# DSO_Front.net
KiCad netlist of a schematic drawn in Altium Designer
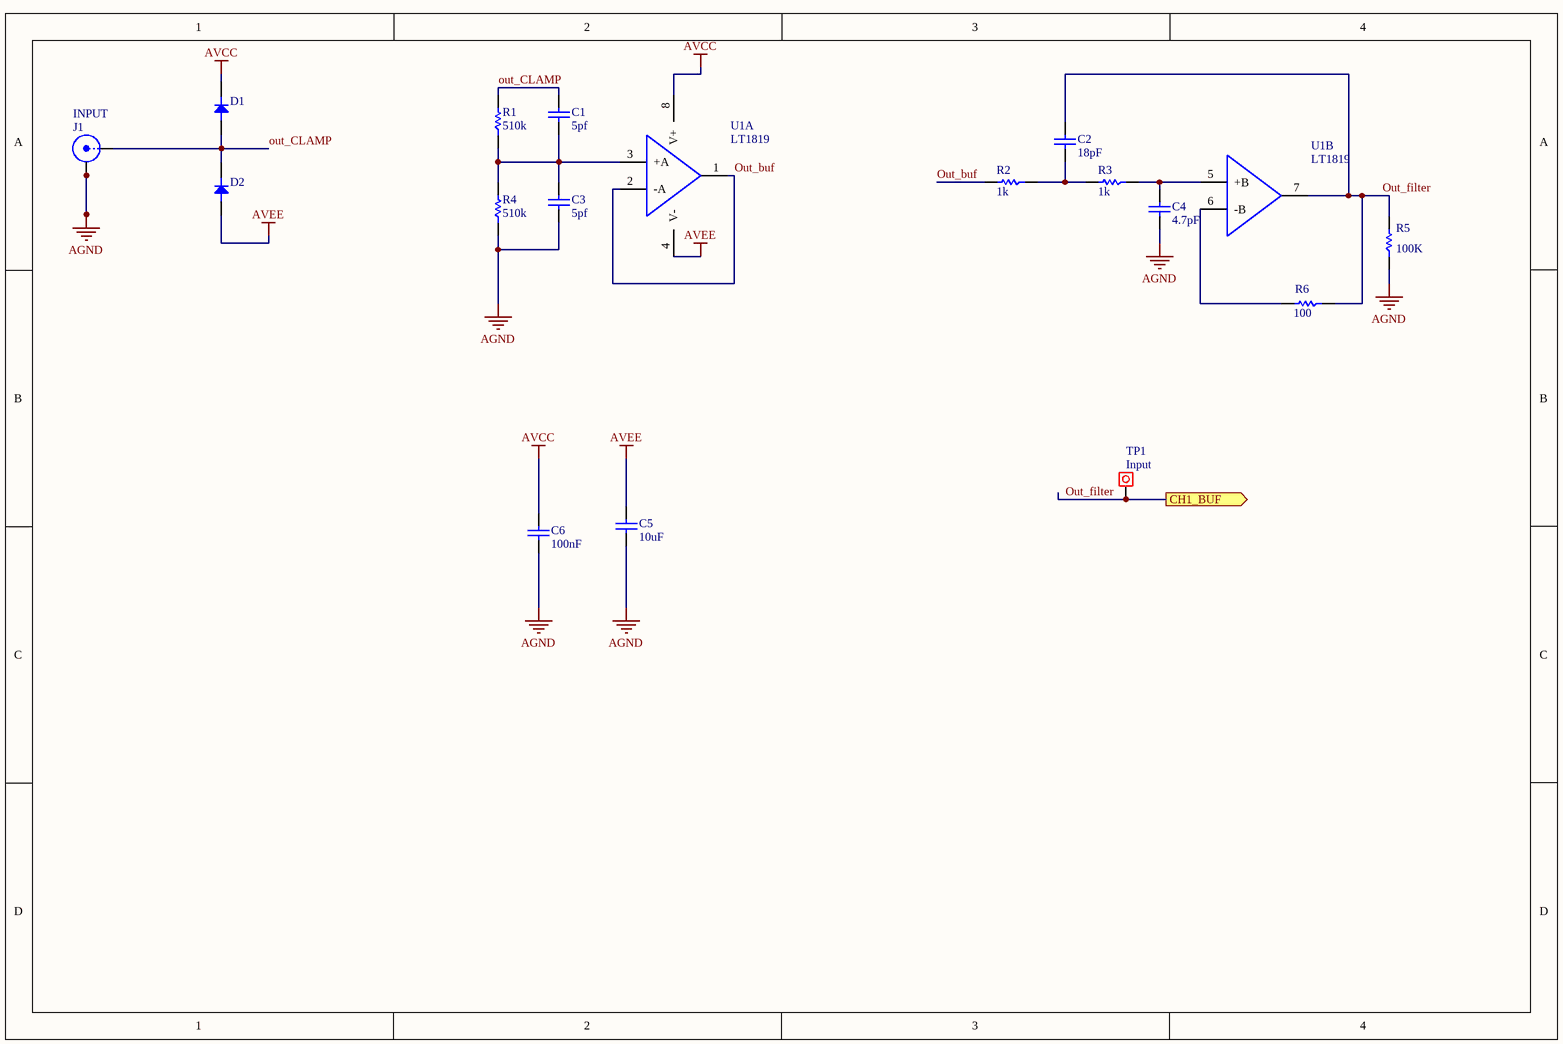
[diagram p0: DSO_Front.SchDoc]

(export (version "E")
  (design (tool "Eeschema 10.0.6"))
  (components
    (comp (ref "C1")
      (value "5pf")
      (footprint "0805C")
      (description "Capacitor")
      (fields (field (name "REVIEWED BY") "RM - 2018/08/05"))
      (libsource (lib "DSO") (part "C"))
    )
    (comp (ref "C2")
      (value "18pF")
      (footprint "0805C")
      (description "Capacitor")
      (fields (field (name "REVIEWED BY") "RM - 2018/08/05"))
      (libsource (lib "DSO") (part "C"))
    )
    (comp (ref "C3")
      (value "5pf")
      (footprint "0805C")
      (description "Capacitor")
      (fields (field (name "REVIEWED BY") "RM - 2018/08/05"))
      (libsource (lib "DSO") (part "C"))
    )
    (comp (ref "C4")
      (value "4.7pF")
      (footprint "0805C")
      (description "Capacitor")
      (fields (field (name "REVIEWED BY") "RM - 2018/08/05"))
      (libsource (lib "DSO") (part "C"))
    )
    (comp (ref "C5")
      (value "10uF")
      (footprint "0805C")
      (description "Capacitor")
      (fields (field (name "REVIEWED BY") "RM - 2018/08/05"))
      (libsource (lib "DSO") (part "C"))
    )
    (comp (ref "C6")
      (value "100nF")
      (footprint "0805C")
      (description "Capacitor")
      (fields (field (name "REVIEWED BY") "RM - 2018/08/05"))
      (libsource (lib "DSO") (part "C"))
    )
    (comp (ref "D1")
      (value "Diode")
      (footprint "SOD-123")
      (fields (field (name "REVIEWED BY") "RM - 2018/08/05"))
      (libsource (lib "DSO") (part "D"))
    )
    (comp (ref "D2")
      (value "Diode")
      (footprint "SOD-123")
      (fields (field (name "REVIEWED BY") "RM - 2018/08/05"))
      (libsource (lib "DSO") (part "D"))
    )
    (comp (ref "J1")
      (value "INPUT")
      (footprint "BNC_VERT")
      (description "BNC Straight")
      (fields (field (name "REVIEWED BY") "RM - 2018/08/05"))
      (libsource (lib "DSO") (part "BNC"))
    )
    (comp (ref "R1")
      (value "510k")
      (footprint "0805")
      (description "Resistor")
      (fields (field (name "REVIEWED BY") "RM - 2018/08/05"))
      (libsource (lib "DSO") (part "R"))
    )
    (comp (ref "R2")
      (value "1k")
      (footprint "0805")
      (description "Resistor")
      (fields (field (name "REVIEWED BY") "RM - 2018/08/05"))
      (libsource (lib "DSO") (part "R"))
    )
    (comp (ref "R3")
      (value "1k")
      (footprint "0805")
      (description "Resistor")
      (fields (field (name "REVIEWED BY") "RM - 2018/08/05"))
      (libsource (lib "DSO") (part "R"))
    )
    (comp (ref "R4")
      (value "510k")
      (footprint "0805")
      (description "Resistor")
      (fields (field (name "REVIEWED BY") "RM - 2018/08/05"))
      (libsource (lib "DSO") (part "R"))
    )
    (comp (ref "R5")
      (value "100K")
      (footprint "0805")
      (description "Resistor")
      (fields (field (name "REVIEWED BY") "RM - 2018/08/05"))
      (libsource (lib "DSO") (part "R"))
    )
    (comp (ref "R6")
      (value "100")
      (footprint "0805")
      (description "Resistor")
      (fields (field (name "REVIEWED BY") "RM - 2018/08/05"))
      (libsource (lib "DSO") (part "R"))
    )
    (comp (ref "TP1")
      (value "Input")
      (footprint "Testpoin")
      (description "Pad")
      (fields (field (name "Comment") "INPUT"))
      (libsource (lib "DSO") (part "Test Point"))
    )
    (comp (ref "U1")
      (value "LT1819")
      (footprint "MSOP-8")
      (description "OpAmp High Frequency Dual")
      (fields (field (name "REVIEWED BY") "RM - 2018/08/05"))
      (libsource (lib "DSO") (part "LT1819"))
    )
  )
  (nets
    (net (code "1") (name "/Out_buf") (class "Default")
      (node (ref "R2") (pin "2") (pintype "passive"))
      (node (ref "U1") (pin "1") (pinfunction "OUTA_1") (pintype "passive"))
      (node (ref "U1") (pin "2") (pinfunction "-A_2") (pintype "passive"))
    )
    (net (code "2") (name "/Out_filter") (class "Default")
      (node (ref "C2") (pin "1") (pinfunction "1_1") (pintype "passive"))
      (node (ref "R5") (pin "2") (pintype "passive"))
      (node (ref "R6") (pin "1") (pintype "passive"))
      (node (ref "TP1") (pin "1") (pintype "passive"))
      (node (ref "U1") (pin "7") (pinfunction "OUTB_7") (pintype "passive"))
    )
    (net (code "3") (name "/out_CLAMP") (class "Default")
      (node (ref "C1") (pin "1") (pinfunction "1_1") (pintype "passive"))
      (node (ref "D1") (pin "A") (pinfunction "A_A") (pintype "passive"))
      (node (ref "D2") (pin "K") (pinfunction "K_K") (pintype "passive"))
      (node (ref "J1") (pin "1") (pinfunction "X_1") (pintype "passive"))
      (node (ref "R1") (pin "2") (pintype "passive"))
    )
    (net (code "4") (name "AGND") (class "Default")
      (node (ref "C3") (pin "2") (pinfunction "2_2") (pintype "passive"))
      (node (ref "C4") (pin "2") (pinfunction "2_2") (pintype "passive"))
      (node (ref "C5") (pin "2") (pinfunction "2_2") (pintype "passive"))
      (node (ref "C6") (pin "2") (pinfunction "2_2") (pintype "passive"))
      (node (ref "J1") (pin "2") (pinfunction "Y_2") (pintype "passive"))
      (node (ref "J1") (pin "3") (pinfunction "Y_3") (pintype "passive"))
      (node (ref "J1") (pin "4") (pinfunction "Y_4") (pintype "passive"))
      (node (ref "J1") (pin "5") (pinfunction "Y_5") (pintype "passive"))
      (node (ref "R4") (pin "1") (pintype "passive"))
      (node (ref "R5") (pin "1") (pintype "passive"))
    )
    (net (code "5") (name "AVCC") (class "Default")
      (node (ref "C6") (pin "1") (pinfunction "1_1") (pintype "passive"))
      (node (ref "D1") (pin "K") (pinfunction "K_K") (pintype "passive"))
      (node (ref "U1") (pin "8") (pinfunction "V+_8") (pintype "passive"))
    )
    (net (code "6") (name "AVEE") (class "Default")
      (node (ref "C5") (pin "1") (pinfunction "1_1") (pintype "passive"))
      (node (ref "D2") (pin "A") (pinfunction "A_A") (pintype "passive"))
      (node (ref "U1") (pin "4") (pinfunction "V-_4") (pintype "passive"))
    )
    (net (code "7") (name "Net-(C2-Pad2)") (class "Default")
      (node (ref "C2") (pin "2") (pinfunction "2_2") (pintype "passive"))
      (node (ref "R2") (pin "1") (pintype "passive"))
      (node (ref "R3") (pin "2") (pintype "passive"))
    )
    (net (code "8") (name "Net-(U1A-+A)") (class "Default")
      (node (ref "C1") (pin "2") (pinfunction "2_2") (pintype "passive"))
      (node (ref "C3") (pin "1") (pinfunction "1_1") (pintype "passive"))
      (node (ref "R1") (pin "1") (pintype "passive"))
      (node (ref "R4") (pin "2") (pintype "passive"))
      (node (ref "U1") (pin "3") (pinfunction "+A_3") (pintype "passive"))
    )
    (net (code "9") (name "Net-(U1B-+B)") (class "Default")
      (node (ref "C4") (pin "1") (pinfunction "1_1") (pintype "passive"))
      (node (ref "R3") (pin "1") (pintype "passive"))
      (node (ref "U1") (pin "5") (pinfunction "+B_5") (pintype "passive"))
    )
    (net (code "10") (name "Net-(U1B--B)") (class "Default")
      (node (ref "R6") (pin "2") (pintype "passive"))
      (node (ref "U1") (pin "6") (pinfunction "-B_6") (pintype "passive"))
    )
  )
)
